# r8_ATMega328.net
KiCad netlist of a schematic drawn in EAGLE
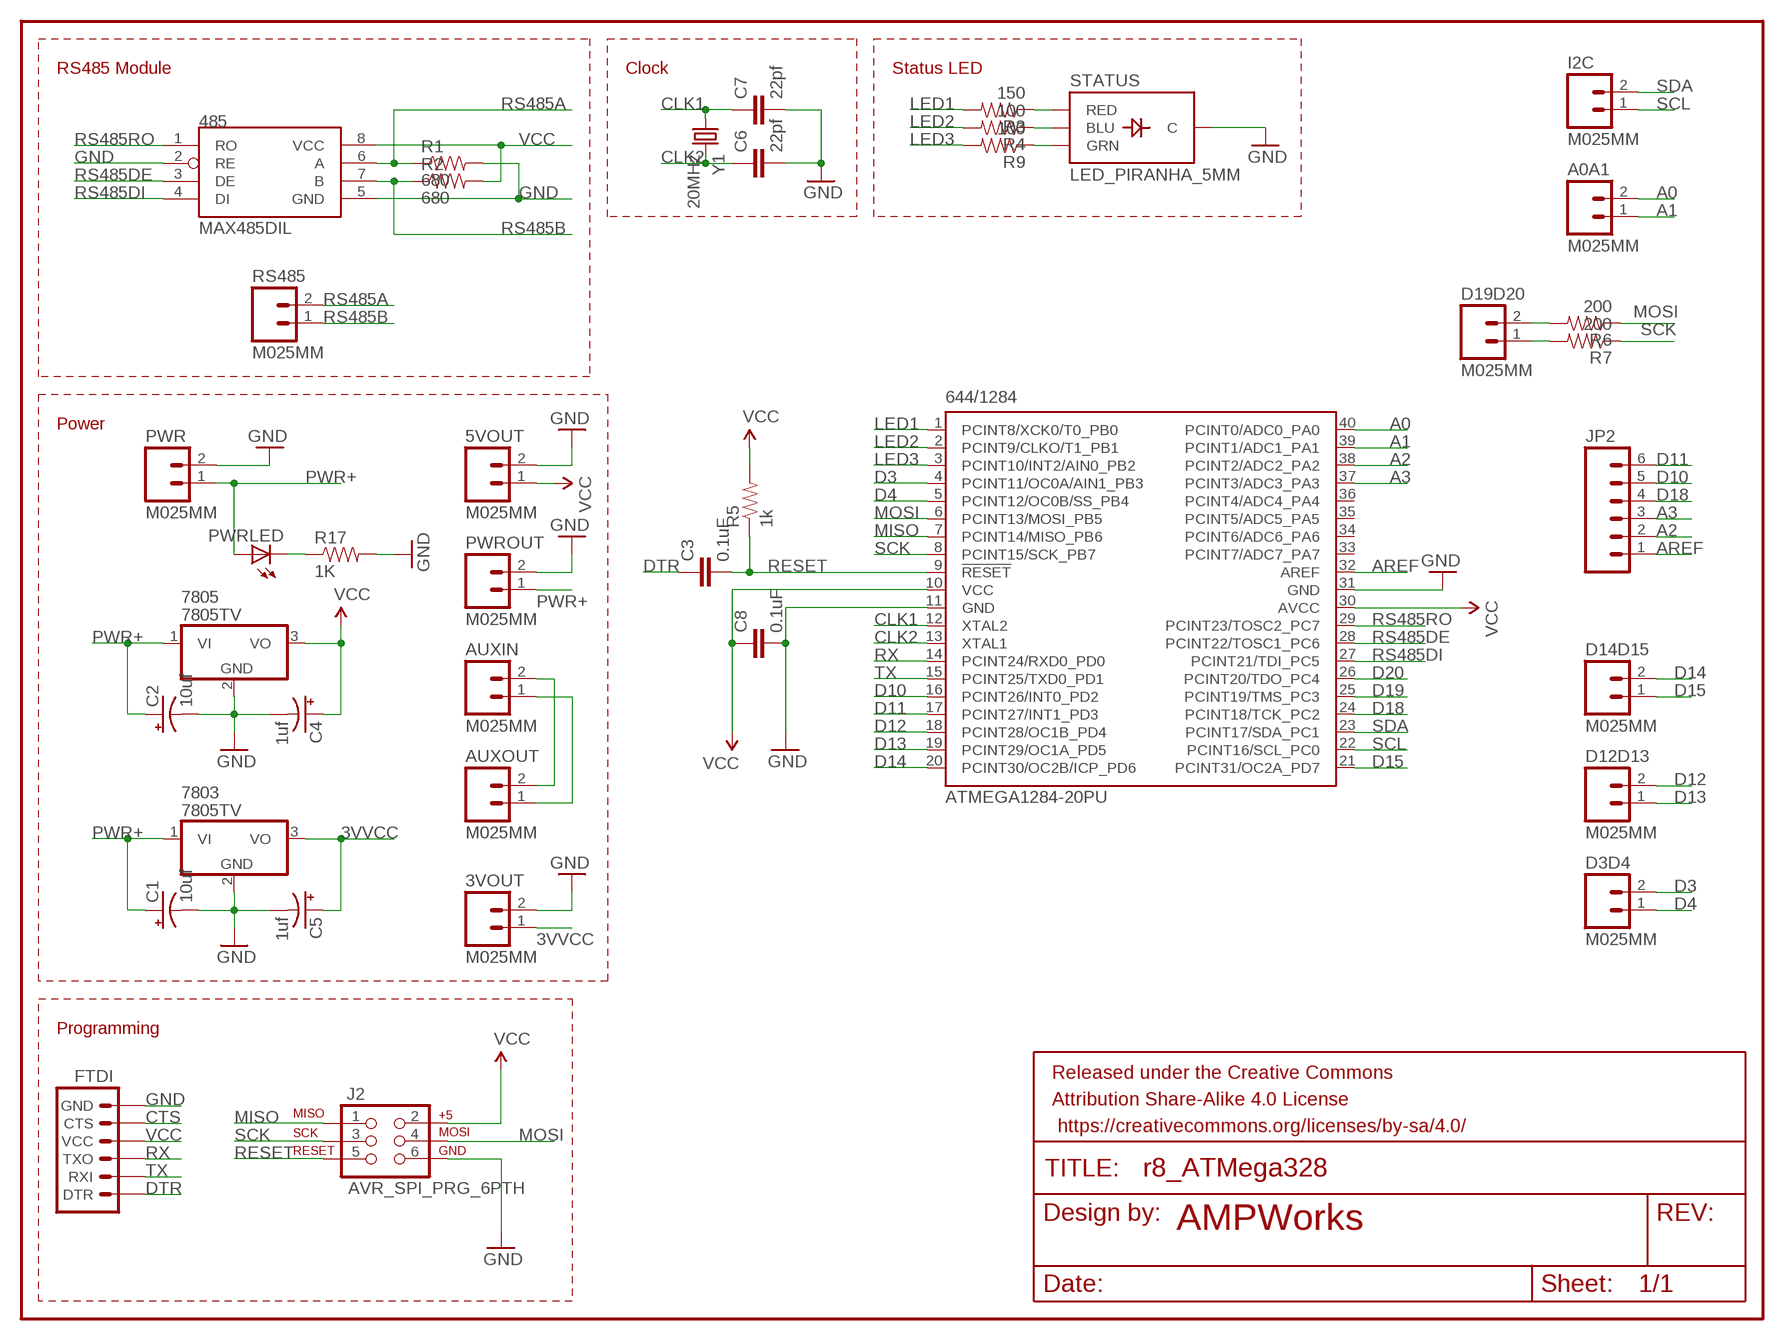
[diagram p0: schematic, sheet 1]

(export (version "E")
  (design (tool "Eeschema 10.0.6"))
  (components
    (comp (ref "3VOUT")
      (value "M025MM")
      (footprint "eagle-import:SCREWTERMINAL-5MM-2")
      (libsource (lib "eagle-import") (part "M025MM"))
    )
    (comp (ref "5VOUT")
      (value "M025MM")
      (footprint "eagle-import:SCREWTERMINAL-5MM-2")
      (libsource (lib "eagle-import") (part "M025MM"))
    )
    (comp (ref "485")
      (value "MAX485DIL")
      (footprint "eagle-import:DIL08")
      (libsource (lib "eagle-import") (part "MAX485DIL"))
    )
    (comp (ref "644/1284")
      (value "ATMEGA1284-20PU")
      (footprint "eagle-import:DIL40")
      (fields (field (name "MPN") "ATMEGA644-20PU"))
      (libsource (lib "eagle-import") (part "ATMEGA644-PU20"))
    )
    (comp (ref "7803")
      (value "7805TV")
      (footprint "eagle-import:TO220V")
      (libsource (lib "eagle-import") (part "78TV05"))
    )
    (comp (ref "7805")
      (value "7805TV")
      (footprint "eagle-import:TO220V")
      (libsource (lib "eagle-import") (part "78TV05"))
    )
    (comp (ref "A0A1")
      (value "M025MM")
      (footprint "eagle-import:SCREWTERMINAL-5MM-2")
      (libsource (lib "eagle-import") (part "M025MM"))
    )
    (comp (ref "AUXIN")
      (value "M025MM")
      (footprint "eagle-import:SCREWTERMINAL-5MM-2")
      (libsource (lib "eagle-import") (part "M025MM"))
    )
    (comp (ref "AUXOUT")
      (value "M025MM")
      (footprint "eagle-import:SCREWTERMINAL-5MM-2")
      (libsource (lib "eagle-import") (part "M025MM"))
    )
    (comp (ref "C1")
      (value "10uf")
      (footprint "eagle-import:CPOL-RADIAL-10UF-25V")
      (libsource (lib "eagle-import") (part "CAP_POLPTH2"))
    )
    (comp (ref "C2")
      (value "10uf")
      (footprint "eagle-import:CPOL-RADIAL-10UF-25V")
      (libsource (lib "eagle-import") (part "CAP_POLPTH2"))
    )
    (comp (ref "C3")
      (value "0.1uF")
      (footprint "eagle-import:CAP-PTH-SMALL")
      (libsource (lib "eagle-import") (part "CAPPTH"))
    )
    (comp (ref "C4")
      (value "1uf")
      (footprint "eagle-import:CPOL-RADIAL-10UF-25V")
      (libsource (lib "eagle-import") (part "CAP_POLPTH2"))
    )
    (comp (ref "C5")
      (value "1uf")
      (footprint "eagle-import:CPOL-RADIAL-10UF-25V")
      (libsource (lib "eagle-import") (part "CAP_POLPTH2"))
    )
    (comp (ref "C6")
      (value "22pf")
      (footprint "eagle-import:CAP-PTH-SMALL")
      (libsource (lib "eagle-import") (part "CAPPTH"))
    )
    (comp (ref "C7")
      (value "22pf")
      (footprint "eagle-import:CAP-PTH-SMALL")
      (libsource (lib "eagle-import") (part "CAPPTH"))
    )
    (comp (ref "C8")
      (value "0.1uF")
      (footprint "eagle-import:CAP-PTH-SMALL")
      (libsource (lib "eagle-import") (part "CAPPTH"))
    )
    (comp (ref "D3D4")
      (value "M025MM")
      (footprint "eagle-import:SCREWTERMINAL-5MM-2")
      (libsource (lib "eagle-import") (part "M025MM"))
    )
    (comp (ref "D12D13")
      (value "M025MM")
      (footprint "eagle-import:SCREWTERMINAL-5MM-2")
      (libsource (lib "eagle-import") (part "M025MM"))
    )
    (comp (ref "D14D15")
      (value "M025MM")
      (footprint "eagle-import:SCREWTERMINAL-5MM-2")
      (libsource (lib "eagle-import") (part "M025MM"))
    )
    (comp (ref "D19D20")
      (value "M025MM")
      (footprint "eagle-import:SCREWTERMINAL-5MM-2")
      (libsource (lib "eagle-import") (part "M025MM"))
    )
    (comp (ref "FRAME1")
      (value "FRAME-LETTER")
      (footprint "eagle-import:CREATIVE_COMMONS")
      (libsource (lib "eagle-import") (part "FRAME-LETTER"))
    )
    (comp (ref "FTDI")
      (value "ARDUINO_SERIAL_PROGRAMPTH")
      (footprint "eagle-import:1X06")
      (libsource (lib "eagle-import") (part "ARDUINO_SERIAL_PROGRAMPTH"))
    )
    (comp (ref "I2C")
      (value "M025MM")
      (footprint "eagle-import:SCREWTERMINAL-5MM-2")
      (libsource (lib "eagle-import") (part "M025MM"))
    )
    (comp (ref "J2")
      (value "AVR_SPI_PRG_6PTH")
      (footprint "eagle-import:2X3")
      (libsource (lib "eagle-import") (part "AVR_SPI_PRG_6PTH"))
    )
    (comp (ref "JP2")
      (value "M06NO_SILK")
      (footprint "eagle-import:1X06_NO_SILK")
      (libsource (lib "eagle-import") (part "M06NO_SILK"))
    )
    (comp (ref "PWR")
      (value "M025MM")
      (footprint "eagle-import:SCREWTERMINAL-5MM-2")
      (libsource (lib "eagle-import") (part "M025MM"))
    )
    (comp (ref "PWRLED")
      (value "LED5MM")
      (footprint "eagle-import:LED5MM")
      (libsource (lib "eagle-import") (part "LED5MM"))
    )
    (comp (ref "PWROUT")
      (value "M025MM")
      (footprint "eagle-import:SCREWTERMINAL-5MM-2")
      (libsource (lib "eagle-import") (part "M025MM"))
    )
    (comp (ref "R1")
      (value "680")
      (footprint "eagle-import:AXIAL-0.4")
      (libsource (lib "eagle-import") (part "SparkFun-Resistors_RESISTORPTH-1/4W"))
    )
    (comp (ref "R2")
      (value "680")
      (footprint "eagle-import:AXIAL-0.4")
      (libsource (lib "eagle-import") (part "SparkFun-Resistors_RESISTORPTH-1/4W"))
    )
    (comp (ref "R3")
      (value "150")
      (footprint "eagle-import:AXIAL-0.4")
      (libsource (lib "eagle-import") (part "RESISTORPTH-1/4W"))
    )
    (comp (ref "R4")
      (value "100")
      (footprint "eagle-import:AXIAL-0.4")
      (libsource (lib "eagle-import") (part "RESISTORPTH-1/4W"))
    )
    (comp (ref "R5")
      (value "1k")
      (footprint "eagle-import:AXIAL-0.4")
      (libsource (lib "eagle-import") (part "RESISTORPTH-1/4W"))
    )
    (comp (ref "R6")
      (value "200")
      (footprint "eagle-import:AXIAL-0.4")
      (libsource (lib "eagle-import") (part "RESISTORPTH-1/4W"))
    )
    (comp (ref "R7")
      (value "200")
      (footprint "eagle-import:AXIAL-0.4")
      (libsource (lib "eagle-import") (part "RESISTORPTH-1/4W"))
    )
    (comp (ref "R9")
      (value "100")
      (footprint "eagle-import:AXIAL-0.4")
      (libsource (lib "eagle-import") (part "RESISTORPTH-1/4W"))
    )
    (comp (ref "R17")
      (value "1K")
      (footprint "eagle-import:AXIAL-0.4")
      (libsource (lib "eagle-import") (part "SparkFun-Resistors_RESISTORPTH-1/4W"))
    )
    (comp (ref "RS485")
      (value "M025MM")
      (footprint "eagle-import:SCREWTERMINAL-5MM-2")
      (libsource (lib "eagle-import") (part "M025MM"))
    )
    (comp (ref "STATUS")
      (value "LED_PIRANHA_5MM")
      (footprint "eagle-import:LED_PIRANHA_5MM")
      (libsource (lib "eagle-import") (part "LED_PIRANHA_5MM"))
    )
    (comp (ref "Y1")
      (value "20MHz")
      (footprint "eagle-import:HC49US")
      (libsource (lib "eagle-import") (part "CRYSTALHC49US"))
    )
  )
  (nets
    (net (code "1") (name "/3VVCC") (class "Default")
      (node (ref "3VOUT") (pin "1") (pinfunction "1_1") (pintype "passive"))
      (node (ref "7803") (pin "3") (pinfunction "VO_3") (pintype "passive"))
      (node (ref "C5") (pin "1") (pinfunction "+_1") (pintype "passive"))
    )
    (net (code "2") (name "/A0") (class "Default")
      (node (ref "644/1284") (pin "40") (pinfunction "PCINT0/ADC0_PA0_40") (pintype "bidirectional"))
      (node (ref "A0A1") (pin "2") (pinfunction "2_2") (pintype "passive"))
    )
    (net (code "3") (name "/A1") (class "Default")
      (node (ref "644/1284") (pin "39") (pinfunction "PCINT1/ADC1_PA1_39") (pintype "bidirectional"))
      (node (ref "A0A1") (pin "1") (pinfunction "1_1") (pintype "passive"))
    )
    (net (code "4") (name "/A2") (class "Default")
      (node (ref "644/1284") (pin "38") (pinfunction "PCINT2/ADC2_PA2_38") (pintype "bidirectional"))
      (node (ref "JP2") (pin "2") (pinfunction "2_2") (pintype "passive"))
    )
    (net (code "5") (name "/A3") (class "Default")
      (node (ref "644/1284") (pin "37") (pinfunction "PCINT3/ADC3_PA3_37") (pintype "bidirectional"))
      (node (ref "JP2") (pin "3") (pinfunction "3_3") (pintype "passive"))
    )
    (net (code "6") (name "/AREF") (class "Default")
      (node (ref "644/1284") (pin "32") (pinfunction "AREF_32") (pintype "passive"))
      (node (ref "JP2") (pin "1") (pinfunction "1_1") (pintype "passive"))
    )
    (net (code "7") (name "/CLK1") (class "Default")
      (node (ref "644/1284") (pin "12") (pinfunction "XTAL2_12") (pintype "output"))
      (node (ref "C7") (pin "1") (pinfunction "1_1") (pintype "passive"))
      (node (ref "Y1") (pin "1") (pinfunction "1_1") (pintype "passive"))
    )
    (net (code "8") (name "/CLK2") (class "Default")
      (node (ref "644/1284") (pin "13") (pinfunction "XTAL1_13") (pintype "input"))
      (node (ref "C6") (pin "1") (pinfunction "1_1") (pintype "passive"))
      (node (ref "Y1") (pin "2") (pinfunction "2_2") (pintype "passive"))
    )
    (net (code "9") (name "/CTS") (class "Default")
      (node (ref "FTDI") (pin "CTS") (pinfunction "CTS_CTS") (pintype "passive"))
    )
    (net (code "10") (name "/D3") (class "Default")
      (node (ref "644/1284") (pin "4") (pinfunction "PCINT11/OC0A/AIN1_PB3_4") (pintype "bidirectional"))
      (node (ref "D3D4") (pin "2") (pinfunction "2_2") (pintype "passive"))
    )
    (net (code "11") (name "/D4") (class "Default")
      (node (ref "644/1284") (pin "5") (pinfunction "PCINT12/OC0B/SS_PB4_5") (pintype "bidirectional"))
      (node (ref "D3D4") (pin "1") (pinfunction "1_1") (pintype "passive"))
    )
    (net (code "12") (name "/D10") (class "Default")
      (node (ref "644/1284") (pin "16") (pinfunction "PCINT26/INT0_PD2_16") (pintype "bidirectional"))
      (node (ref "JP2") (pin "5") (pinfunction "5_5") (pintype "passive"))
    )
    (net (code "13") (name "/D11") (class "Default")
      (node (ref "644/1284") (pin "17") (pinfunction "PCINT27/INT1_PD3_17") (pintype "bidirectional"))
      (node (ref "JP2") (pin "6") (pinfunction "6_6") (pintype "passive"))
    )
    (net (code "14") (name "/D12") (class "Default")
      (node (ref "644/1284") (pin "18") (pinfunction "PCINT28/OC1B_PD4_18") (pintype "bidirectional"))
      (node (ref "D12D13") (pin "2") (pinfunction "2_2") (pintype "passive"))
    )
    (net (code "15") (name "/D13") (class "Default")
      (node (ref "644/1284") (pin "19") (pinfunction "PCINT29/OC1A_PD5_19") (pintype "bidirectional"))
      (node (ref "D12D13") (pin "1") (pinfunction "1_1") (pintype "passive"))
    )
    (net (code "16") (name "/D14") (class "Default")
      (node (ref "644/1284") (pin "20") (pinfunction "PCINT30/OC2B/ICP_PD6_20") (pintype "bidirectional"))
      (node (ref "D14D15") (pin "2") (pinfunction "2_2") (pintype "passive"))
    )
    (net (code "17") (name "/D15") (class "Default")
      (node (ref "644/1284") (pin "21") (pinfunction "PCINT31/OC2A_PD7_21") (pintype "bidirectional"))
      (node (ref "D14D15") (pin "1") (pinfunction "1_1") (pintype "passive"))
    )
    (net (code "18") (name "/D18") (class "Default")
      (node (ref "644/1284") (pin "24") (pinfunction "PCINT18/TCK_PC2_24") (pintype "bidirectional"))
      (node (ref "JP2") (pin "4") (pinfunction "4_4") (pintype "passive"))
    )
    (net (code "19") (name "/D19") (class "Default")
      (node (ref "644/1284") (pin "25") (pinfunction "PCINT19/TMS_PC3_25") (pintype "bidirectional"))
    )
    (net (code "20") (name "/D20") (class "Default")
      (node (ref "644/1284") (pin "26") (pinfunction "PCINT20/TDO_PC4_26") (pintype "bidirectional"))
    )
    (net (code "21") (name "/DTR") (class "Default")
      (node (ref "C3") (pin "1") (pinfunction "1_1") (pintype "passive"))
      (node (ref "FTDI") (pin "DTR") (pinfunction "DTR_DTR") (pintype "passive"))
    )
    (net (code "22") (name "/LED1") (class "Default")
      (node (ref "644/1284") (pin "1") (pinfunction "PCINT8/XCK0/T0_PB0_1") (pintype "bidirectional"))
      (node (ref "R3") (pin "P$2") (pinfunction "2_P$2") (pintype "passive"))
    )
    (net (code "23") (name "/LED2") (class "Default")
      (node (ref "644/1284") (pin "2") (pinfunction "PCINT9/CLKO/T1_PB1_2") (pintype "bidirectional"))
      (node (ref "R4") (pin "P$2") (pinfunction "2_P$2") (pintype "passive"))
    )
    (net (code "24") (name "/LED3") (class "Default")
      (node (ref "644/1284") (pin "3") (pinfunction "PCINT10/INT2/AIN0_PB2_3") (pintype "bidirectional"))
      (node (ref "R9") (pin "P$2") (pinfunction "2_P$2") (pintype "passive"))
    )
    (net (code "25") (name "/MISO") (class "Default")
      (node (ref "644/1284") (pin "7") (pinfunction "PCINT14/MISO_PB6_7") (pintype "bidirectional"))
      (node (ref "J2") (pin "1") (pinfunction "1_1") (pintype "passive"))
    )
    (net (code "26") (name "/MOSI") (class "Default")
      (node (ref "644/1284") (pin "6") (pinfunction "PCINT13/MOSI_PB5_6") (pintype "bidirectional"))
      (node (ref "J2") (pin "4") (pinfunction "4_4") (pintype "passive"))
      (node (ref "R6") (pin "P$1") (pinfunction "1_P$1") (pintype "passive"))
    )
    (net (code "27") (name "/PWR+") (class "Default")
      (node (ref "7803") (pin "1") (pinfunction "VI_1") (pintype "input"))
      (node (ref "7805") (pin "1") (pinfunction "VI_1") (pintype "input"))
      (node (ref "C1") (pin "1") (pinfunction "+_1") (pintype "passive"))
      (node (ref "C2") (pin "1") (pinfunction "+_1") (pintype "passive"))
      (node (ref "PWR") (pin "1") (pinfunction "1_1") (pintype "passive"))
      (node (ref "PWRLED") (pin "A") (pinfunction "A_A") (pintype "passive"))
      (node (ref "PWROUT") (pin "1") (pinfunction "1_1") (pintype "passive"))
    )
    (net (code "28") (name "/RESET") (class "Default")
      (node (ref "644/1284") (pin "9") (pinfunction "~{RESET}_9") (pintype "input"))
      (node (ref "C3") (pin "2") (pinfunction "2_2") (pintype "passive"))
      (node (ref "J2") (pin "5") (pinfunction "5_5") (pintype "passive"))
      (node (ref "R5") (pin "P$1") (pinfunction "1_P$1") (pintype "passive"))
    )
    (net (code "29") (name "/RS485A") (class "Default")
      (node (ref "485") (pin "6") (pinfunction "A_6") (pintype "bidirectional"))
      (node (ref "R1") (pin "P$1") (pinfunction "1_P$1") (pintype "passive"))
      (node (ref "RS485") (pin "2") (pinfunction "2_2") (pintype "passive"))
    )
    (net (code "30") (name "/RS485B") (class "Default")
      (node (ref "485") (pin "7") (pinfunction "B_7") (pintype "bidirectional"))
      (node (ref "R2") (pin "P$1") (pinfunction "1_P$1") (pintype "passive"))
      (node (ref "RS485") (pin "1") (pinfunction "1_1") (pintype "passive"))
    )
    (net (code "31") (name "/RS485DE") (class "Default")
      (node (ref "485") (pin "3") (pinfunction "DE_3") (pintype "bidirectional"))
      (node (ref "644/1284") (pin "28") (pinfunction "PCINT22/TOSC1_PC6_28") (pintype "bidirectional"))
    )
    (net (code "32") (name "/RS485DI") (class "Default")
      (node (ref "485") (pin "4") (pinfunction "DI_4") (pintype "bidirectional"))
      (node (ref "644/1284") (pin "27") (pinfunction "PCINT21/TDI_PC5_27") (pintype "bidirectional"))
    )
    (net (code "33") (name "/RS485RO") (class "Default")
      (node (ref "485") (pin "1") (pinfunction "RO_1") (pintype "bidirectional"))
      (node (ref "644/1284") (pin "29") (pinfunction "PCINT23/TOSC2_PC7_29") (pintype "bidirectional"))
    )
    (net (code "34") (name "/RX") (class "Default")
      (node (ref "644/1284") (pin "14") (pinfunction "PCINT24/RXD0_PD0_14") (pintype "bidirectional"))
      (node (ref "FTDI") (pin "TXO") (pinfunction "TXO_TXO") (pintype "passive"))
    )
    (net (code "35") (name "/SCK") (class "Default")
      (node (ref "644/1284") (pin "8") (pinfunction "PCINT15/SCK_PB7_8") (pintype "bidirectional"))
      (node (ref "J2") (pin "3") (pinfunction "3_3") (pintype "passive"))
      (node (ref "R7") (pin "P$1") (pinfunction "1_P$1") (pintype "passive"))
    )
    (net (code "36") (name "/SCL") (class "Default")
      (node (ref "644/1284") (pin "22") (pinfunction "PCINT16/SCL_PC0_22") (pintype "bidirectional"))
      (node (ref "I2C") (pin "1") (pinfunction "1_1") (pintype "passive"))
    )
    (net (code "37") (name "/SDA") (class "Default")
      (node (ref "644/1284") (pin "23") (pinfunction "PCINT17/SDA_PC1_23") (pintype "bidirectional"))
      (node (ref "I2C") (pin "2") (pinfunction "2_2") (pintype "passive"))
    )
    (net (code "38") (name "/TX") (class "Default")
      (node (ref "644/1284") (pin "15") (pinfunction "PCINT25/TXD0_PD1_15") (pintype "bidirectional"))
      (node (ref "FTDI") (pin "RXI") (pinfunction "RXI_RXI") (pintype "passive"))
    )
    (net (code "39") (name "GND") (class "Default")
      (node (ref "3VOUT") (pin "2") (pinfunction "2_2") (pintype "passive"))
      (node (ref "485") (pin "2") (pinfunction "RE_2") (pintype "bidirectional"))
      (node (ref "485") (pin "5") (pinfunction "GND_5") (pintype "bidirectional"))
      (node (ref "5VOUT") (pin "2") (pinfunction "2_2") (pintype "passive"))
      (node (ref "644/1284") (pin "11") (pinfunction "GND_11") (pintype "power_in"))
      (node (ref "644/1284") (pin "31") (pinfunction "GND_31") (pintype "power_in"))
      (node (ref "7803") (pin "2") (pinfunction "GND_2") (pintype "passive"))
      (node (ref "7805") (pin "2") (pinfunction "GND_2") (pintype "passive"))
      (node (ref "C1") (pin "2") (pinfunction "-_2") (pintype "passive"))
      (node (ref "C2") (pin "2") (pinfunction "-_2") (pintype "passive"))
      (node (ref "C4") (pin "2") (pinfunction "-_2") (pintype "passive"))
      (node (ref "C5") (pin "2") (pinfunction "-_2") (pintype "passive"))
      (node (ref "C6") (pin "2") (pinfunction "2_2") (pintype "passive"))
      (node (ref "C7") (pin "2") (pinfunction "2_2") (pintype "passive"))
      (node (ref "C8") (pin "2") (pinfunction "2_2") (pintype "passive"))
      (node (ref "FTDI") (pin "GND") (pinfunction "GND_GND") (pintype "passive"))
      (node (ref "J2") (pin "6") (pinfunction "6_6") (pintype "passive"))
      (node (ref "PWR") (pin "2") (pinfunction "2_2") (pintype "passive"))
      (node (ref "PWROUT") (pin "2") (pinfunction "2_2") (pintype "passive"))
      (node (ref "R1") (pin "P$2") (pinfunction "2_P$2") (pintype "passive"))
      (node (ref "R17") (pin "P$2") (pinfunction "2_P$2") (pintype "passive"))
      (node (ref "STATUS") (pin "-") (pinfunction "C_-") (pintype "bidirectional"))
    )
    (net (code "40") (name "Net-(AUXIN-Pad1)") (class "Default")
      (node (ref "AUXIN") (pin "1") (pinfunction "1_1") (pintype "passive"))
      (node (ref "AUXOUT") (pin "1") (pinfunction "1_1") (pintype "passive"))
    )
    (net (code "41") (name "Net-(AUXIN-Pad2)") (class "Default")
      (node (ref "AUXIN") (pin "2") (pinfunction "2_2") (pintype "passive"))
      (node (ref "AUXOUT") (pin "2") (pinfunction "2_2") (pintype "passive"))
    )
    (net (code "42") (name "Net-(PWRLED-C)") (class "Default")
      (node (ref "PWRLED") (pin "K") (pinfunction "C_K") (pintype "passive"))
      (node (ref "R17") (pin "P$1") (pinfunction "1_P$1") (pintype "passive"))
    )
    (net (code "43") (name "Net-(R3-1)") (class "Default")
      (node (ref "R3") (pin "P$1") (pinfunction "1_P$1") (pintype "passive"))
      (node (ref "STATUS") (pin "R") (pinfunction "RED_R") (pintype "bidirectional"))
    )
    (net (code "44") (name "Net-(R4-1)") (class "Default")
      (node (ref "R4") (pin "P$1") (pinfunction "1_P$1") (pintype "passive"))
      (node (ref "STATUS") (pin "B") (pinfunction "BLU_B") (pintype "bidirectional"))
    )
    (net (code "45") (name "Net-(R6-2)") (class "Default")
      (node (ref "D19D20") (pin "2") (pinfunction "2_2") (pintype "passive"))
      (node (ref "R6") (pin "P$2") (pinfunction "2_P$2") (pintype "passive"))
    )
    (net (code "46") (name "Net-(R7-2)") (class "Default")
      (node (ref "D19D20") (pin "1") (pinfunction "1_1") (pintype "passive"))
      (node (ref "R7") (pin "P$2") (pinfunction "2_P$2") (pintype "passive"))
    )
    (net (code "47") (name "Net-(R9-1)") (class "Default")
      (node (ref "R9") (pin "P$1") (pinfunction "1_P$1") (pintype "passive"))
      (node (ref "STATUS") (pin "G") (pinfunction "GRN_G") (pintype "bidirectional"))
    )
    (net (code "48") (name "VCC") (class "Default")
      (node (ref "485") (pin "8") (pinfunction "VCC_8") (pintype "bidirectional"))
      (node (ref "5VOUT") (pin "1") (pinfunction "1_1") (pintype "passive"))
      (node (ref "644/1284") (pin "10") (pinfunction "VCC_10") (pintype "power_in"))
      (node (ref "644/1284") (pin "30") (pinfunction "AVCC_30") (pintype "power_in"))
      (node (ref "7805") (pin "3") (pinfunction "VO_3") (pintype "passive"))
      (node (ref "C4") (pin "1") (pinfunction "+_1") (pintype "passive"))
      (node (ref "C8") (pin "1") (pinfunction "1_1") (pintype "passive"))
      (node (ref "FTDI") (pin "VCC") (pinfunction "VCC_VCC") (pintype "passive"))
      (node (ref "J2") (pin "2") (pinfunction "2_2") (pintype "passive"))
      (node (ref "R2") (pin "P$2") (pinfunction "2_P$2") (pintype "passive"))
      (node (ref "R5") (pin "P$2") (pinfunction "2_P$2") (pintype "passive"))
    )
    (net (code "49") (name "unconnected-(644/1284-PCINT4{slash}ADC4_PA4-Pad36)") (class "Default")
      (node (ref "644/1284") (pin "36") (pinfunction "PCINT4/ADC4_PA4_36") (pintype "bidirectional"))
    )
    (net (code "50") (name "unconnected-(644/1284-PCINT5{slash}ADC5_PA5-Pad35)") (class "Default")
      (node (ref "644/1284") (pin "35") (pinfunction "PCINT5/ADC5_PA5_35") (pintype "bidirectional"))
    )
    (net (code "51") (name "unconnected-(644/1284-PCINT6{slash}ADC6_PA6-Pad34)") (class "Default")
      (node (ref "644/1284") (pin "34") (pinfunction "PCINT6/ADC6_PA6_34") (pintype "bidirectional"))
    )
    (net (code "52") (name "unconnected-(644/1284-PCINT7{slash}ADC7_PA7-Pad33)") (class "Default")
      (node (ref "644/1284") (pin "33") (pinfunction "PCINT7/ADC7_PA7_33") (pintype "bidirectional"))
    )
  )
)
